# LEDsButtons.net
KiCad netlist of a schematic drawn in Altium Designer
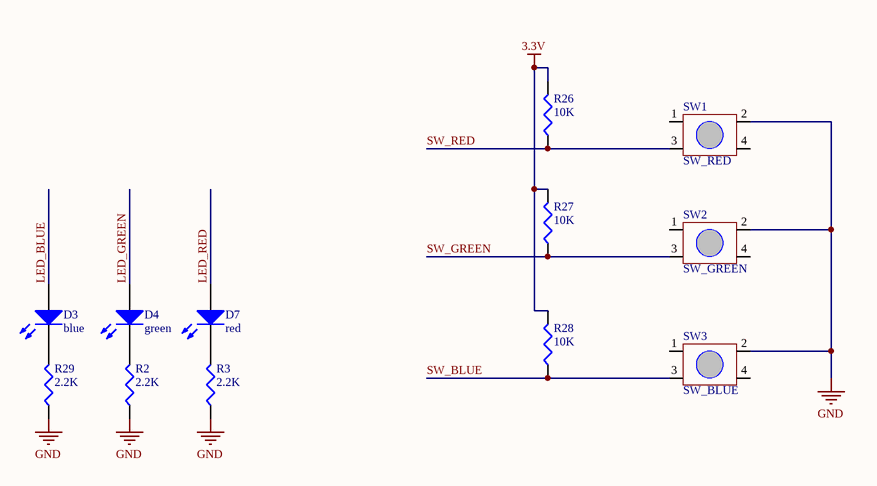
[diagram p0: LEDsButtons.SchDoc]

(export (version "E")
  (design (tool "Eeschema 10.0.6"))
  (components
    (comp (ref "D3") (value "blue") (footprint "SurfaceMount(603)") (libsource (lib "mrone") (part "LED")))
    (comp (ref "D4") (value "green") (footprint "SurfaceMount(603)") (libsource (lib "mrone") (part "LED")))
    (comp (ref "D7") (value "red") (footprint "SurfaceMount(603)") (libsource (lib "mrone") (part "LED")))
    (comp (ref "R2")
      (value "2.2K")
      (footprint "J1-0603")
      (description "Resistor")
      (fields (field (name "Comment") "Res3") (field (name "PUBLISHER") "Altium Limited"))
      (libsource (lib "Miscellaneous Devices") (part "Res3"))
    )
    (comp (ref "R3")
      (value "2.2K")
      (footprint "J1-0603")
      (description "Resistor")
      (fields (field (name "Comment") "Res3") (field (name "PUBLISHER") "Altium Limited"))
      (libsource (lib "Miscellaneous Devices") (part "Res3"))
    )
    (comp (ref "R26")
      (value "10K")
      (footprint "J1-0603")
      (description "Resistor")
      (fields (field (name "Comment") "Res3") (field (name "PUBLISHER") "Altium Limited"))
      (libsource (lib "Miscellaneous Devices") (part "Res3"))
    )
    (comp (ref "R27")
      (value "10K")
      (footprint "J1-0603")
      (description "Resistor")
      (fields (field (name "Comment") "Res3") (field (name "PUBLISHER") "Altium Limited"))
      (libsource (lib "Miscellaneous Devices") (part "Res3"))
    )
    (comp (ref "R28")
      (value "10K")
      (footprint "J1-0603")
      (description "Resistor")
      (fields (field (name "Comment") "Res3") (field (name "PUBLISHER") "Altium Limited"))
      (libsource (lib "Miscellaneous Devices") (part "Res3"))
    )
    (comp (ref "R29")
      (value "2.2K")
      (footprint "J1-0603")
      (description "Resistor")
      (fields (field (name "Comment") "Res3") (field (name "PUBLISHER") "Altium Limited"))
      (libsource (lib "Miscellaneous Devices") (part "Res3"))
    )
    (comp (ref "SW1")
      (value "SW_RED")
      (footprint "SwitchTall-TL330")
      (libsource (lib "mrone") (part "Switch-TL330"))
    )
    (comp (ref "SW2")
      (value "SW_GREEN")
      (footprint "SwitchTall-TL330")
      (libsource (lib "mrone") (part "Switch-TL330"))
    )
    (comp (ref "SW3")
      (value "SW_BLUE")
      (footprint "SwitchTall-TL330")
      (libsource (lib "mrone") (part "Switch-TL330"))
    )
  )
  (nets
    (net (code "1") (name "/LED_BLUE") (class "Default")
      (node (ref "D3") (pin "1") (pinfunction "A_1") (pintype "passive"))
    )
    (net (code "2") (name "/LED_GREEN") (class "Default")
      (node (ref "D4") (pin "1") (pinfunction "A_1") (pintype "passive"))
    )
    (net (code "3") (name "/LED_RED") (class "Default")
      (node (ref "D7") (pin "1") (pinfunction "A_1") (pintype "passive"))
    )
    (net (code "4") (name "/SW_BLUE") (class "Default")
      (node (ref "R28") (pin "1") (pinfunction "1_1") (pintype "passive"))
      (node (ref "SW3") (pin "3") (pinfunction "3_3") (pintype "passive"))
    )
    (net (code "5") (name "/SW_GREEN") (class "Default")
      (node (ref "R27") (pin "1") (pinfunction "1_1") (pintype "passive"))
      (node (ref "SW2") (pin "3") (pinfunction "3_3") (pintype "passive"))
    )
    (net (code "6") (name "/SW_RED") (class "Default")
      (node (ref "R26") (pin "1") (pinfunction "1_1") (pintype "passive"))
      (node (ref "SW1") (pin "3") (pinfunction "3_3") (pintype "passive"))
    )
    (net (code "7") (name "3.3V") (class "Default")
      (node (ref "R26") (pin "2") (pinfunction "2_2") (pintype "passive"))
      (node (ref "R27") (pin "2") (pinfunction "2_2") (pintype "passive"))
      (node (ref "R28") (pin "2") (pinfunction "2_2") (pintype "passive"))
    )
    (net (code "8") (name "GND") (class "Default")
      (node (ref "R2") (pin "1") (pinfunction "1_1") (pintype "passive"))
      (node (ref "R29") (pin "1") (pinfunction "1_1") (pintype "passive"))
      (node (ref "R3") (pin "1") (pinfunction "1_1") (pintype "passive"))
      (node (ref "SW1") (pin "2") (pinfunction "2_2") (pintype "passive"))
      (node (ref "SW2") (pin "2") (pinfunction "2_2") (pintype "passive"))
      (node (ref "SW3") (pin "2") (pinfunction "2_2") (pintype "passive"))
    )
    (net (code "9") (name "Net-(D3-K)") (class "Default")
      (node (ref "D3") (pin "2") (pinfunction "K_2") (pintype "passive"))
      (node (ref "R29") (pin "2") (pinfunction "2_2") (pintype "passive"))
    )
    (net (code "10") (name "Net-(D4-K)") (class "Default")
      (node (ref "D4") (pin "2") (pinfunction "K_2") (pintype "passive"))
      (node (ref "R2") (pin "2") (pinfunction "2_2") (pintype "passive"))
    )
    (net (code "11") (name "Net-(D7-K)") (class "Default")
      (node (ref "D7") (pin "2") (pinfunction "K_2") (pintype "passive"))
      (node (ref "R3") (pin "2") (pinfunction "2_2") (pintype "passive"))
    )
    (net (code "12") (name "unconnected-(SW1-Pad1)") (class "Default")
      (node (ref "SW1") (pin "1") (pinfunction "1_1") (pintype "passive"))
    )
    (net (code "13") (name "unconnected-(SW1-Pad4)") (class "Default")
      (node (ref "SW1") (pin "4") (pinfunction "4_4") (pintype "passive"))
    )
    (net (code "14") (name "unconnected-(SW2-Pad1)") (class "Default")
      (node (ref "SW2") (pin "1") (pinfunction "1_1") (pintype "passive"))
    )
    (net (code "15") (name "unconnected-(SW2-Pad4)") (class "Default")
      (node (ref "SW2") (pin "4") (pinfunction "4_4") (pintype "passive"))
    )
    (net (code "16") (name "unconnected-(SW3-Pad1)") (class "Default")
      (node (ref "SW3") (pin "1") (pinfunction "1_1") (pintype "passive"))
    )
    (net (code "17") (name "unconnected-(SW3-Pad4)") (class "Default")
      (node (ref "SW3") (pin "4") (pinfunction "4_4") (pintype "passive"))
    )
  )
)
